# KC_BaseBoard4CompareTest-V0_2-XLR.net
KiCad netlist of a schematic drawn in Altium Designer
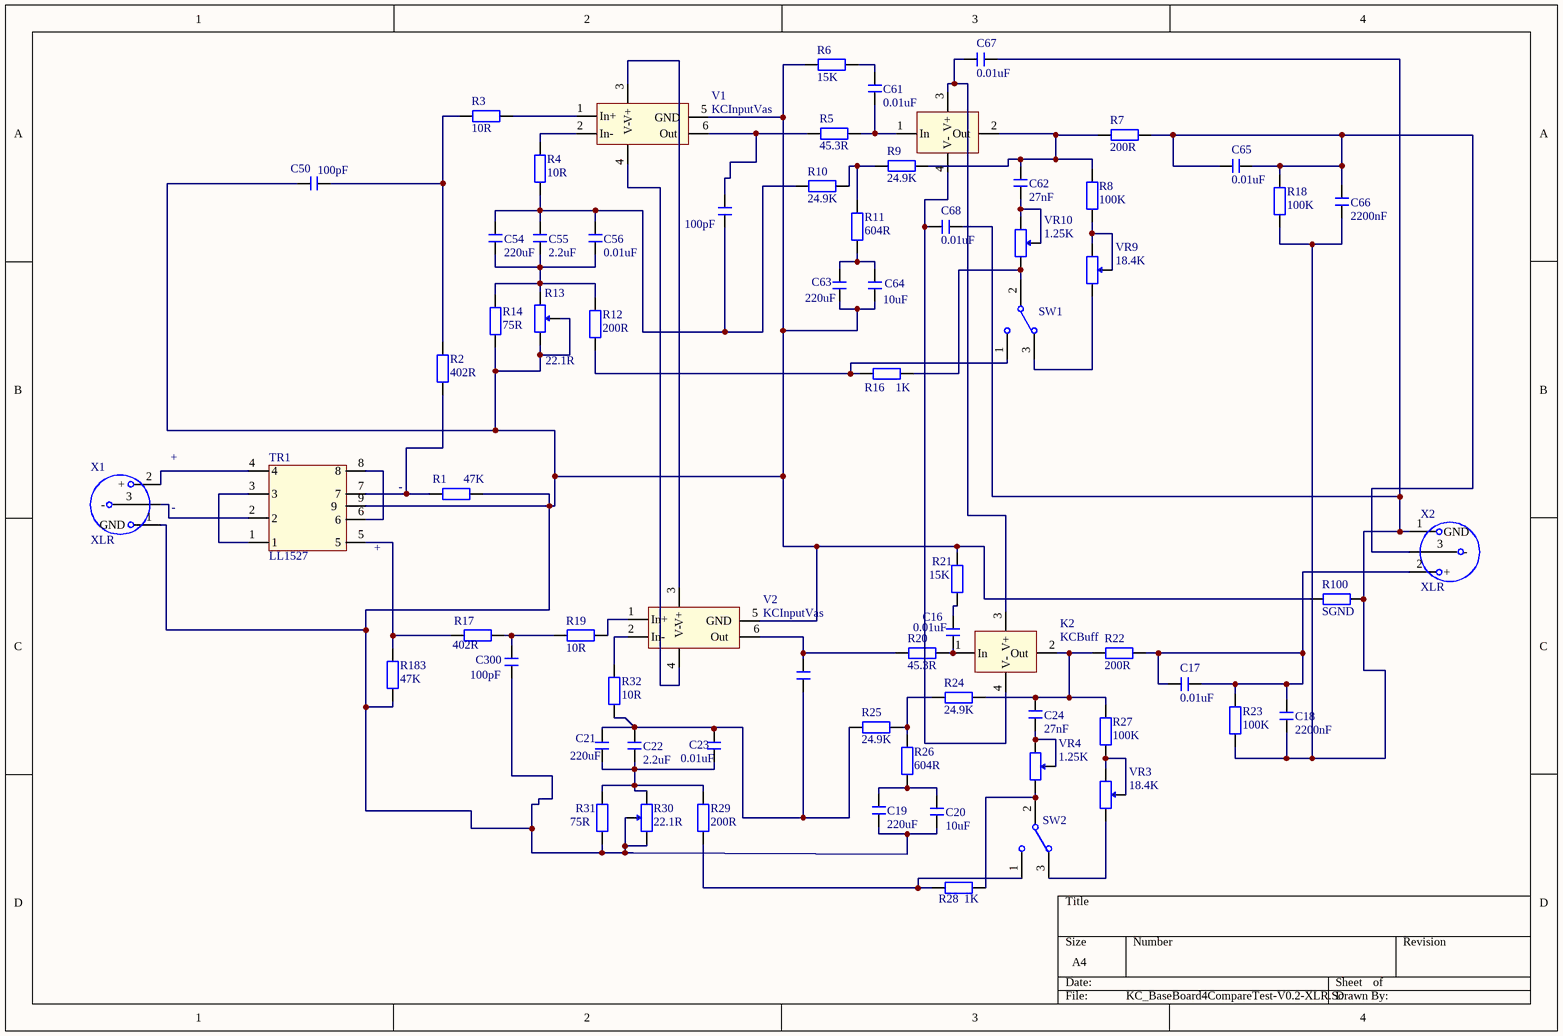
[diagram p0: KC_BaseBoard4CompareTest-V0.2-XLR.SchDoc]

(export (version "E")
  (design (tool "Eeschema 10.0.6"))
  (components
    (comp (ref "C16")
      (value "0.01uF")
      (footprint "CBB 6.3*6.3*5")
      (description "CBB电容")
      (fields (field (name "版权归属") "源创客"))
      (libsource (lib "电阻-电容-电感") (part "C-CBB"))
    )
    (comp (ref "C17")
      (value "0.01uF")
      (footprint "CBB 6.3*6.3*5")
      (description "CBB电容")
      (fields (field (name "版权归属") "源创客"))
      (libsource (lib "电阻-电容-电感") (part "C-CBB"))
    )
    (comp (ref "C18")
      (value "2200nF")
      (footprint "CBB 6.3*6.3*5")
      (description "CBB电容")
      (fields (field (name "版权归属") "源创客"))
      (libsource (lib "电阻-电容-电感") (part "C-CBB"))
    )
    (comp (ref "C19")
      (value "220uF")
      (footprint "CBB 6.3*6.3*5")
      (description "CBB电容")
      (fields (field (name "版权归属") "源创客"))
      (libsource (lib "电阻-电容-电感") (part "C-CBB"))
    )
    (comp (ref "C20")
      (value "10uF")
      (footprint "CBB 6.3*6.3*5")
      (description "CBB电容")
      (fields (field (name "版权归属") "源创客"))
      (libsource (lib "电阻-电容-电感") (part "C-CBB"))
    )
    (comp (ref "C21")
      (value "220uF")
      (footprint "CBB 6.3*6.3*5")
      (description "CBB电容")
      (fields (field (name "版权归属") "源创客"))
      (libsource (lib "电阻-电容-电感") (part "C-CBB"))
    )
    (comp (ref "C22")
      (value "2.2uF")
      (footprint "CBB 6.3*6.3*5")
      (description "CBB电容")
      (fields (field (name "版权归属") "源创客"))
      (libsource (lib "电阻-电容-电感") (part "C-CBB"))
    )
    (comp (ref "C23")
      (value "0.01uF")
      (footprint "CBB 6.3*6.3*5")
      (description "CBB电容")
      (fields (field (name "版权归属") "源创客"))
      (libsource (lib "电阻-电容-电感") (part "C-CBB"))
    )
    (comp (ref "C24")
      (value "27nF")
      (footprint "CBB 6.3*6.3*5")
      (description "CBB电容")
      (fields (field (name "版权归属") "源创客"))
      (libsource (lib "电阻-电容-电感") (part "C-CBB"))
    )
    (comp (ref "C50")
      (value "100pF")
      (footprint "CBB 6.3*6.3*5")
      (description "CBB电容")
      (fields (field (name "版权归属") "源创客"))
      (libsource (lib "电阻-电容-电感") (part "C-CBB"))
    )
    (comp (ref "C54")
      (value "220uF")
      (footprint "CBB 6.3*6.3*5")
      (description "CBB电容")
      (fields (field (name "版权归属") "源创客"))
      (libsource (lib "电阻-电容-电感") (part "C-CBB"))
    )
    (comp (ref "C55")
      (value "2.2uF")
      (footprint "CBB 6.3*6.3*5")
      (description "CBB电容")
      (fields (field (name "版权归属") "源创客"))
      (libsource (lib "电阻-电容-电感") (part "C-CBB"))
    )
    (comp (ref "C56")
      (value "0.01uF")
      (footprint "CBB 6.3*6.3*5")
      (description "CBB电容")
      (fields (field (name "版权归属") "源创客"))
      (libsource (lib "电阻-电容-电感") (part "C-CBB"))
    )
    (comp (ref "C60")
      (value "100pF")
      (footprint "CBB 6.3*6.3*5")
      (description "CBB电容")
      (fields (field (name "版权归属") "源创客"))
      (libsource (lib "电阻-电容-电感") (part "C-CBB"))
    )
    (comp (ref "C61")
      (value "0.01uF")
      (footprint "CBB 6.3*6.3*5")
      (description "CBB电容")
      (fields (field (name "版权归属") "源创客"))
      (libsource (lib "电阻-电容-电感") (part "C-CBB"))
    )
    (comp (ref "C62")
      (value "27nF")
      (footprint "CBB 6.3*6.3*5")
      (description "CBB电容")
      (fields (field (name "版权归属") "源创客"))
      (libsource (lib "电阻-电容-电感") (part "C-CBB"))
    )
    (comp (ref "C63")
      (value "220uF")
      (footprint "CBB 6.3*6.3*5")
      (description "CBB电容")
      (fields (field (name "版权归属") "源创客"))
      (libsource (lib "电阻-电容-电感") (part "C-CBB"))
    )
    (comp (ref "C64")
      (value "10uF")
      (footprint "CBB 6.3*6.3*5")
      (description "CBB电容")
      (fields (field (name "版权归属") "源创客"))
      (libsource (lib "电阻-电容-电感") (part "C-CBB"))
    )
    (comp (ref "C65")
      (value "0.01uF")
      (footprint "CBB 6.3*6.3*5")
      (description "CBB电容")
      (fields (field (name "版权归属") "源创客"))
      (libsource (lib "电阻-电容-电感") (part "C-CBB"))
    )
    (comp (ref "C66")
      (value "2200nF")
      (footprint "CBB 6.3*6.3*5")
      (description "CBB电容")
      (fields (field (name "版权归属") "源创客"))
      (libsource (lib "电阻-电容-电感") (part "C-CBB"))
    )
    (comp (ref "C67")
      (value "0.01uF")
      (footprint "CBB 6.3*6.3*5")
      (description "CBB电容")
      (fields (field (name "版权归属") "源创客"))
      (libsource (lib "电阻-电容-电感") (part "C-CBB"))
    )
    (comp (ref "C68")
      (value "0.01uF")
      (footprint "CBB 6.3*6.3*5")
      (description "CBB电容")
      (fields (field (name "版权归属") "源创客"))
      (libsource (lib "电阻-电容-电感") (part "C-CBB"))
    )
    (comp (ref "C300")
      (value "100pF")
      (footprint "CBB 6.3*6.3*5")
      (description "CBB电容")
      (fields (field (name "版权归属") "源创客"))
      (libsource (lib "电阻-电容-电感") (part "C-CBB"))
    )
    (comp (ref "C403")
      (value "100pF")
      (footprint "CBB 6.3*6.3*5")
      (description "CBB电容")
      (fields (field (name "版权归属") "源创客"))
      (libsource (lib "电阻-电容-电感") (part "C-CBB"))
    )
    (comp (ref "K1")
      (value "KCBuff")
      (footprint "KCBuff")
      (description "King Cello Buffer Stage")
      (libsource (lib "KC_amp") (part "KCBuff"))
    )
    (comp (ref "K2")
      (value "KCBuff")
      (footprint "KCBuff_M4")
      (description "King Cello Buffer Stage")
      (libsource (lib "KC_amp") (part "KCBuff"))
    )
    (comp (ref "R1")
      (value "47K")
      (footprint "RS 1/4W")
      (description "直插色环电阻")
      (fields (field (name "版权归属") "源创客"))
      (libsource (lib "电阻-电容-电感") (part "R-CRR"))
    )
    (comp (ref "R2")
      (value "402R")
      (footprint "RS 1/4W")
      (description "直插色环电阻")
      (fields (field (name "版权归属") "源创客"))
      (libsource (lib "电阻-电容-电感") (part "R-CRR"))
    )
    (comp (ref "R3")
      (value "10R")
      (footprint "RS 1/4W")
      (description "直插色环电阻")
      (fields (field (name "版权归属") "源创客"))
      (libsource (lib "电阻-电容-电感") (part "R-CRR"))
    )
    (comp (ref "R4")
      (value "10R")
      (footprint "RS 1/4W")
      (description "直插色环电阻")
      (fields (field (name "版权归属") "源创客"))
      (libsource (lib "电阻-电容-电感") (part "R-CRR"))
    )
    (comp (ref "R5")
      (value "45.3R")
      (footprint "RS 1/4W")
      (description "直插色环电阻")
      (fields (field (name "版权归属") "源创客"))
      (libsource (lib "电阻-电容-电感") (part "R-CRR"))
    )
    (comp (ref "R6")
      (value "15K")
      (footprint "RS 1/4W")
      (description "直插色环电阻")
      (fields (field (name "版权归属") "源创客"))
      (libsource (lib "电阻-电容-电感") (part "R-CRR"))
    )
    (comp (ref "R7")
      (value "200R")
      (footprint "RS 1/4W")
      (description "直插色环电阻")
      (fields (field (name "版权归属") "源创客"))
      (libsource (lib "电阻-电容-电感") (part "R-CRR"))
    )
    (comp (ref "R8")
      (value "100K")
      (footprint "RS 1/4W")
      (description "直插色环电阻")
      (fields (field (name "版权归属") "源创客"))
      (libsource (lib "电阻-电容-电感") (part "R-CRR"))
    )
    (comp (ref "R9")
      (value "24.9K")
      (footprint "RS 1/4W")
      (description "直插色环电阻")
      (fields (field (name "版权归属") "源创客"))
      (libsource (lib "电阻-电容-电感") (part "R-CRR"))
    )
    (comp (ref "R10")
      (value "24.9K")
      (footprint "RS 1/4W")
      (description "直插色环电阻")
      (fields (field (name "版权归属") "源创客"))
      (libsource (lib "电阻-电容-电感") (part "R-CRR"))
    )
    (comp (ref "R11")
      (value "604R")
      (footprint "RS 1/4W")
      (description "直插色环电阻")
      (fields (field (name "版权归属") "源创客"))
      (libsource (lib "电阻-电容-电感") (part "R-CRR"))
    )
    (comp (ref "R12")
      (value "200R")
      (footprint "RS 1/4W")
      (description "直插色环电阻")
      (fields (field (name "版权归属") "源创客"))
      (libsource (lib "电阻-电容-电感") (part "R-CRR"))
    )
    (comp (ref "R13")
      (value "22.1R")
      (footprint "RS 1/2W-VR")
      (description "直插可调电阻-顶调")
      (libsource (lib "电阻-电容-电感") (part "VR-W"))
    )
    (comp (ref "R14")
      (value "75R")
      (footprint "RS 1/4W")
      (description "直插色环电阻")
      (fields (field (name "版权归属") "源创客"))
      (libsource (lib "电阻-电容-电感") (part "R-CRR"))
    )
    (comp (ref "R16")
      (value "1K")
      (footprint "RS 1/4W")
      (description "直插色环电阻")
      (fields (field (name "版权归属") "源创客"))
      (libsource (lib "电阻-电容-电感") (part "R-CRR"))
    )
    (comp (ref "R17")
      (value "402R")
      (footprint "RS 1/4W")
      (description "直插色环电阻")
      (fields (field (name "版权归属") "源创客"))
      (libsource (lib "电阻-电容-电感") (part "R-CRR"))
    )
    (comp (ref "R18")
      (value "100K")
      (footprint "RS 1/4W")
      (description "直插色环电阻")
      (fields (field (name "版权归属") "源创客"))
      (libsource (lib "电阻-电容-电感") (part "R-CRR"))
    )
    (comp (ref "R19")
      (value "10R")
      (footprint "RS 1/4W")
      (description "直插色环电阻")
      (fields (field (name "版权归属") "源创客"))
      (libsource (lib "电阻-电容-电感") (part "R-CRR"))
    )
    (comp (ref "R20")
      (value "45.3R")
      (footprint "RS 1/4W")
      (description "直插色环电阻")
      (fields (field (name "版权归属") "源创客"))
      (libsource (lib "电阻-电容-电感") (part "R-CRR"))
    )
    (comp (ref "R21")
      (value "15K")
      (footprint "RS 1/4W")
      (description "直插色环电阻")
      (fields (field (name "版权归属") "源创客"))
      (libsource (lib "电阻-电容-电感") (part "R-CRR"))
    )
    (comp (ref "R22")
      (value "200R")
      (footprint "RS 1/4W")
      (description "直插色环电阻")
      (fields (field (name "版权归属") "源创客"))
      (libsource (lib "电阻-电容-电感") (part "R-CRR"))
    )
    (comp (ref "R23")
      (value "100K")
      (footprint "RS 1/4W")
      (description "直插色环电阻")
      (fields (field (name "版权归属") "源创客"))
      (libsource (lib "电阻-电容-电感") (part "R-CRR"))
    )
    (comp (ref "R24")
      (value "24.9K")
      (footprint "RS 1/4W")
      (description "直插色环电阻")
      (fields (field (name "版权归属") "源创客"))
      (libsource (lib "电阻-电容-电感") (part "R-CRR"))
    )
    (comp (ref "R25")
      (value "24.9K")
      (footprint "RS 1/4W")
      (description "直插色环电阻")
      (fields (field (name "版权归属") "源创客"))
      (libsource (lib "电阻-电容-电感") (part "R-CRR"))
    )
    (comp (ref "R26")
      (value "604R")
      (footprint "RS 1/4W")
      (description "直插色环电阻")
      (fields (field (name "版权归属") "源创客"))
      (libsource (lib "电阻-电容-电感") (part "R-CRR"))
    )
    (comp (ref "R27")
      (value "100K")
      (footprint "RS 1/4W")
      (description "直插色环电阻")
      (fields (field (name "版权归属") "源创客"))
      (libsource (lib "电阻-电容-电感") (part "R-CRR"))
    )
    (comp (ref "R28")
      (value "1K")
      (footprint "RS 1/4W")
      (description "直插色环电阻")
      (fields (field (name "版权归属") "源创客"))
      (libsource (lib "电阻-电容-电感") (part "R-CRR"))
    )
    (comp (ref "R29")
      (value "200R")
      (footprint "RS 1/4W")
      (description "直插色环电阻")
      (fields (field (name "版权归属") "源创客"))
      (libsource (lib "电阻-电容-电感") (part "R-CRR"))
    )
    (comp (ref "R30")
      (value "22.1R")
      (footprint "RS 1/2W-VR")
      (description "直插可调电阻-顶调")
      (libsource (lib "电阻-电容-电感") (part "VR-W"))
    )
    (comp (ref "R31")
      (value "75R")
      (footprint "RS 1/4W")
      (description "直插色环电阻")
      (fields (field (name "版权归属") "源创客"))
      (libsource (lib "电阻-电容-电感") (part "R-CRR"))
    )
    (comp (ref "R32")
      (value "10R")
      (footprint "RS 1/4W")
      (description "直插色环电阻")
      (fields (field (name "版权归属") "源创客"))
      (libsource (lib "电阻-电容-电感") (part "R-CRR"))
    )
    (comp (ref "R100")
      (value "SGND")
      (footprint "RS 1/4W")
      (description "直插色环电阻")
      (fields (field (name "版权归属") "源创客"))
      (libsource (lib "电阻-电容-电感") (part "R-CRR"))
    )
    (comp (ref "R183")
      (value "47K")
      (footprint "RS 1/4W")
      (description "直插色环电阻")
      (fields (field (name "版权归属") "源创客"))
      (libsource (lib "电阻-电容-电感") (part "R-CRR"))
    )
    (comp (ref "SW1")
      (value "SW-3P-2S")
      (footprint "SS-12D06")
      (description "3 Pin 2 Switch")
      (libsource (lib "Connectors") (part "SW-3P-2S"))
    )
    (comp (ref "SW2")
      (value "SW-3P-2S")
      (footprint "SS-12D06")
      (description "3 Pin 2 Switch")
      (libsource (lib "Connectors") (part "SW-3P-2S"))
    )
    (comp (ref "TR1")
      (value "LL1527")
      (footprint "LL1527")
      (description "Lundahl LL1527")
      (libsource (lib "KC_amp") (part "LL1527"))
    )
    (comp (ref "V1")
      (value "KCInputVas")
      (footprint "KCIn_VAS")
      (description "King Cello Input Stage and VAS")
      (libsource (lib "KC_amp") (part "KCInputVas"))
    )
    (comp (ref "V2")
      (value "KCInputVas")
      (footprint "KCIn_VAS")
      (description "King Cello Input Stage and VAS")
      (libsource (lib "KC_amp") (part "KCInputVas"))
    )
    (comp (ref "VR3")
      (value "18.4K")
      (footprint "RS 1/2W-VR")
      (description "直插可调电阻-顶调")
      (libsource (lib "电阻-电容-电感") (part "VR-W"))
    )
    (comp (ref "VR4")
      (value "1.25K")
      (footprint "RS 1/2W-VR")
      (description "直插可调电阻-顶调")
      (libsource (lib "电阻-电容-电感") (part "VR-W"))
    )
    (comp (ref "VR9")
      (value "18.4K")
      (footprint "RS 1/2W-VR")
      (description "直插可调电阻-顶调")
      (libsource (lib "电阻-电容-电感") (part "VR-W"))
    )
    (comp (ref "VR10")
      (value "1.25K")
      (footprint "RS 1/2W-VR")
      (description "直插可调电阻-顶调")
      (libsource (lib "电阻-电容-电感") (part "VR-W"))
    )
    (comp (ref "X1")
      (value "XLR")
      (footprint "XLR-Male")
      (description "3 Pin XLR")
      (libsource (lib "Connectors") (part "XLR"))
    )
    (comp (ref "X2")
      (value "XLR")
      (footprint "XLR-Male")
      (description "3 Pin XLR")
      (libsource (lib "Connectors") (part "XLR"))
    )
  )
  (nets
    (net (code "1") (name "Net-(C16-Pad2)") (class "Default")
      (node (ref "C16") (pin "2") (pinfunction "2_2") (pintype "passive"))
      (node (ref "R21") (pin "1") (pinfunction "1_1") (pintype "passive"))
    )
    (net (code "2") (name "Net-(C19-Pad1)") (class "Default")
      (node (ref "C19") (pin "1") (pinfunction "1_1") (pintype "passive"))
      (node (ref "C20") (pin "1") (pinfunction "1_1") (pintype "passive"))
      (node (ref "R26") (pin "1") (pinfunction "1_1") (pintype "passive"))
    )
    (net (code "3") (name "Net-(C21-Pad1)") (class "Default")
      (node (ref "C21") (pin "1") (pinfunction "1_1") (pintype "passive"))
      (node (ref "C22") (pin "1") (pinfunction "1_1") (pintype "passive"))
      (node (ref "C23") (pin "1") (pinfunction "1_1") (pintype "passive"))
      (node (ref "C403") (pin "1") (pinfunction "1_1") (pintype "passive"))
      (node (ref "R25") (pin "1") (pinfunction "1_1") (pintype "passive"))
      (node (ref "R32") (pin "1") (pinfunction "1_1") (pintype "passive"))
    )
    (net (code "4") (name "Net-(C21-Pad2)") (class "Default")
      (node (ref "C21") (pin "2") (pinfunction "2_2") (pintype "passive"))
      (node (ref "C22") (pin "2") (pinfunction "2_2") (pintype "passive"))
      (node (ref "C23") (pin "2") (pinfunction "2_2") (pintype "passive"))
      (node (ref "R29") (pin "2") (pinfunction "2_2") (pintype "passive"))
      (node (ref "R30") (pin "2") (pinfunction "2_2") (pintype "passive"))
      (node (ref "R31") (pin "2") (pinfunction "2_2") (pintype "passive"))
    )
    (net (code "5") (name "Net-(C24-Pad2)") (class "Default")
      (node (ref "C24") (pin "2") (pinfunction "2_2") (pintype "passive"))
      (node (ref "VR4") (pin "1") (pinfunction "1_1") (pintype "passive"))
      (node (ref "VR4") (pin "3") (pinfunction "3_3") (pintype "passive"))
    )
    (net (code "6") (name "Net-(C50-Pad2)") (class "Default")
      (node (ref "C50") (pin "2") (pinfunction "2_2") (pintype "passive"))
      (node (ref "R2") (pin "2") (pinfunction "2_2") (pintype "passive"))
      (node (ref "R3") (pin "1") (pinfunction "1_1") (pintype "passive"))
    )
    (net (code "7") (name "Net-(C54-Pad1)") (class "Default")
      (node (ref "C54") (pin "1") (pinfunction "1_1") (pintype "passive"))
      (node (ref "C55") (pin "1") (pinfunction "1_1") (pintype "passive"))
      (node (ref "C56") (pin "1") (pinfunction "1_1") (pintype "passive"))
      (node (ref "R12") (pin "1") (pinfunction "1_1") (pintype "passive"))
      (node (ref "R13") (pin "1") (pinfunction "1_1") (pintype "passive"))
      (node (ref "R14") (pin "1") (pinfunction "1_1") (pintype "passive"))
    )
    (net (code "8") (name "Net-(C54-Pad2)") (class "Default")
      (node (ref "C54") (pin "2") (pinfunction "2_2") (pintype "passive"))
      (node (ref "C55") (pin "2") (pinfunction "2_2") (pintype "passive"))
      (node (ref "C56") (pin "2") (pinfunction "2_2") (pintype "passive"))
      (node (ref "C60") (pin "1") (pinfunction "1_1") (pintype "passive"))
      (node (ref "R10") (pin "2") (pinfunction "2_2") (pintype "passive"))
      (node (ref "R4") (pin "1") (pinfunction "1_1") (pintype "passive"))
    )
    (net (code "9") (name "Net-(C61-Pad2)") (class "Default")
      (node (ref "C61") (pin "2") (pinfunction "2_2") (pintype "passive"))
      (node (ref "R6") (pin "1") (pinfunction "1_1") (pintype "passive"))
    )
    (net (code "10") (name "Net-(C62-Pad1)") (class "Default")
      (node (ref "C62") (pin "1") (pinfunction "1_1") (pintype "passive"))
      (node (ref "VR10") (pin "1") (pinfunction "1_1") (pintype "passive"))
      (node (ref "VR10") (pin "3") (pinfunction "3_3") (pintype "passive"))
    )
    (net (code "11") (name "Net-(C63-Pad2)") (class "Default")
      (node (ref "C63") (pin "2") (pinfunction "2_2") (pintype "passive"))
      (node (ref "C64") (pin "2") (pinfunction "2_2") (pintype "passive"))
      (node (ref "R11") (pin "2") (pinfunction "2_2") (pintype "passive"))
    )
    (net (code "12") (name "Net-(C300-Pad2)") (class "Default")
      (node (ref "C300") (pin "2") (pinfunction "2_2") (pintype "passive"))
      (node (ref "R17") (pin "2") (pinfunction "2_2") (pintype "passive"))
      (node (ref "R19") (pin "1") (pinfunction "1_1") (pintype "passive"))
    )
    (net (code "13") (name "Net-(K1-In)") (class "Default")
      (node (ref "C61") (pin "1") (pinfunction "1_1") (pintype "passive"))
      (node (ref "K1") (pin "1") (pinfunction "In_1") (pintype "passive"))
      (node (ref "R5") (pin "2") (pinfunction "2_2") (pintype "passive"))
    )
    (net (code "14") (name "Net-(K1-Out)") (class "Default")
      (node (ref "C62") (pin "2") (pinfunction "2_2") (pintype "passive"))
      (node (ref "K1") (pin "2") (pinfunction "Out_2") (pintype "passive"))
      (node (ref "R7") (pin "1") (pinfunction "1_1") (pintype "passive"))
      (node (ref "R8") (pin "2") (pinfunction "2_2") (pintype "passive"))
      (node (ref "R9") (pin "1") (pinfunction "1_1") (pintype "passive"))
    )
    (net (code "15") (name "Net-(K1-V+)") (class "Default")
      (node (ref "C67") (pin "1") (pinfunction "1_1") (pintype "passive"))
      (node (ref "K1") (pin "3") (pinfunction "V+_3") (pintype "passive"))
      (node (ref "K2") (pin "3") (pinfunction "V+_3") (pintype "passive"))
    )
    (net (code "16") (name "Net-(K1-V-)") (class "Default")
      (node (ref "C68") (pin "1") (pinfunction "1_1") (pintype "passive"))
      (node (ref "K1") (pin "4") (pinfunction "V-_4") (pintype "passive"))
      (node (ref "K2") (pin "4") (pinfunction "V-_4") (pintype "passive"))
    )
    (net (code "17") (name "Net-(K2-In)") (class "Default")
      (node (ref "C16") (pin "1") (pinfunction "1_1") (pintype "passive"))
      (node (ref "K2") (pin "1") (pinfunction "In_1") (pintype "passive"))
      (node (ref "R20") (pin "2") (pinfunction "2_2") (pintype "passive"))
    )
    (net (code "18") (name "Net-(K2-Out)") (class "Default")
      (node (ref "C24") (pin "1") (pinfunction "1_1") (pintype "passive"))
      (node (ref "K2") (pin "2") (pinfunction "Out_2") (pintype "passive"))
      (node (ref "R22") (pin "2") (pinfunction "2_2") (pintype "passive"))
      (node (ref "R24") (pin "2") (pinfunction "2_2") (pintype "passive"))
      (node (ref "R27") (pin "1") (pinfunction "1_1") (pintype "passive"))
    )
    (net (code "19") (name "Net-(R1-Pad1)") (class "Default")
      (node (ref "R1") (pin "1") (pinfunction "1_1") (pintype "passive"))
      (node (ref "R2") (pin "1") (pinfunction "1_1") (pintype "passive"))
      (node (ref "TR1") (pin "7") (pinfunction "7_7") (pintype "passive"))
    )
    (net (code "20") (name "Net-(R8-Pad1)") (class "Default")
      (node (ref "R8") (pin "1") (pinfunction "1_1") (pintype "passive"))
      (node (ref "VR9") (pin "1") (pinfunction "1_1") (pintype "passive"))
      (node (ref "VR9") (pin "3") (pinfunction "3_3") (pintype "passive"))
    )
    (net (code "21") (name "Net-(R10-Pad1)") (class "Default")
      (node (ref "R10") (pin "1") (pinfunction "1_1") (pintype "passive"))
      (node (ref "R11") (pin "1") (pinfunction "1_1") (pintype "passive"))
      (node (ref "R9") (pin "2") (pinfunction "2_2") (pintype "passive"))
    )
    (net (code "22") (name "Net-(R12-Pad2)") (class "Default")
      (node (ref "R12") (pin "2") (pinfunction "2_2") (pintype "passive"))
      (node (ref "R16") (pin "1") (pinfunction "1_1") (pintype "passive"))
      (node (ref "SW1") (pin "1") (pinfunction "1_1") (pintype "passive"))
    )
    (net (code "23") (name "Net-(R16-Pad2)") (class "Default")
      (node (ref "R16") (pin "2") (pinfunction "2_2") (pintype "passive"))
      (node (ref "SW1") (pin "2") (pinfunction "2_2") (pintype "passive"))
      (node (ref "VR10") (pin "2") (pinfunction "2_2") (pintype "passive"))
    )
    (net (code "24") (name "Net-(R17-Pad1)") (class "Default")
      (node (ref "R17") (pin "1") (pinfunction "1_1") (pintype "passive"))
      (node (ref "R183") (pin "2") (pinfunction "2_2") (pintype "passive"))
      (node (ref "TR1") (pin "5") (pinfunction "5_5") (pintype "passive"))
    )
    (net (code "25") (name "Net-(R24-Pad1)") (class "Default")
      (node (ref "R24") (pin "1") (pinfunction "1_1") (pintype "passive"))
      (node (ref "R25") (pin "2") (pinfunction "2_2") (pintype "passive"))
      (node (ref "R26") (pin "2") (pinfunction "2_2") (pintype "passive"))
    )
    (net (code "26") (name "Net-(R27-Pad2)") (class "Default")
      (node (ref "R27") (pin "2") (pinfunction "2_2") (pintype "passive"))
      (node (ref "VR3") (pin "1") (pinfunction "1_1") (pintype "passive"))
      (node (ref "VR3") (pin "3") (pinfunction "3_3") (pintype "passive"))
    )
    (net (code "27") (name "Net-(R28-Pad1)") (class "Default")
      (node (ref "R28") (pin "1") (pinfunction "1_1") (pintype "passive"))
      (node (ref "R29") (pin "1") (pinfunction "1_1") (pintype "passive"))
      (node (ref "SW2") (pin "1") (pinfunction "1_1") (pintype "passive"))
    )
    (net (code "28") (name "Net-(R28-Pad2)") (class "Default")
      (node (ref "R28") (pin "2") (pinfunction "2_2") (pintype "passive"))
      (node (ref "SW2") (pin "2") (pinfunction "2_2") (pintype "passive"))
      (node (ref "VR4") (pin "2") (pinfunction "2_2") (pintype "passive"))
    )
    (net (code "29") (name "Net-(SW1-Pad3)") (class "Default")
      (node (ref "SW1") (pin "3") (pinfunction "3_3") (pintype "passive"))
      (node (ref "VR9") (pin "2") (pinfunction "2_2") (pintype "passive"))
    )
    (net (code "30") (name "Net-(SW2-Pad3)") (class "Default")
      (node (ref "SW2") (pin "3") (pinfunction "3_3") (pintype "passive"))
      (node (ref "VR3") (pin "2") (pinfunction "2_2") (pintype "passive"))
    )
    (net (code "31") (name "Net-(TR1-Pad1)") (class "Default")
      (node (ref "TR1") (pin "1") (pinfunction "1_1") (pintype "passive"))
      (node (ref "TR1") (pin "3") (pinfunction "3_3") (pintype "passive"))
    )
    (net (code "32") (name "Net-(TR1-Pad6)") (class "Default")
      (node (ref "TR1") (pin "6") (pinfunction "6_6") (pintype "passive"))
      (node (ref "TR1") (pin "8") (pinfunction "8_8") (pintype "passive"))
    )
    (net (code "33") (name "Net-(V1-GND)") (class "Default")
      (node (ref "C19") (pin "2") (pinfunction "2_2") (pintype "passive"))
      (node (ref "C20") (pin "2") (pinfunction "2_2") (pintype "passive"))
      (node (ref "C300") (pin "1") (pinfunction "1_1") (pintype "passive"))
      (node (ref "C50") (pin "1") (pinfunction "1_1") (pintype "passive"))
      (node (ref "C63") (pin "1") (pinfunction "1_1") (pintype "passive"))
      (node (ref "C64") (pin "1") (pinfunction "1_1") (pintype "passive"))
      (node (ref "R1") (pin "2") (pinfunction "2_2") (pintype "passive"))
      (node (ref "R100") (pin "1") (pinfunction "1_1") (pintype "passive"))
      (node (ref "R13") (pin "2") (pinfunction "2_2") (pintype "passive"))
      (node (ref "R13") (pin "3") (pinfunction "3_3") (pintype "passive"))
      (node (ref "R14") (pin "2") (pinfunction "2_2") (pintype "passive"))
      (node (ref "R183") (pin "1") (pinfunction "1_1") (pintype "passive"))
      (node (ref "R21") (pin "2") (pinfunction "2_2") (pintype "passive"))
      (node (ref "R30") (pin "1") (pinfunction "1_1") (pintype "passive"))
      (node (ref "R30") (pin "3") (pinfunction "3_3") (pintype "passive"))
      (node (ref "R31") (pin "1") (pinfunction "1_1") (pintype "passive"))
      (node (ref "R6") (pin "2") (pinfunction "2_2") (pintype "passive"))
      (node (ref "TR1") (pin "9") (pinfunction "9_9") (pintype "passive"))
      (node (ref "V1") (pin "5") (pinfunction "GND_5") (pintype "passive"))
      (node (ref "V2") (pin "5") (pinfunction "GND_5") (pintype "passive"))
      (node (ref "X1") (pin "1") (pinfunction "GND_1") (pintype "passive"))
    )
    (net (code "34") (name "Net-(V1-In+)") (class "Default")
      (node (ref "R3") (pin "2") (pinfunction "2_2") (pintype "passive"))
      (node (ref "V1") (pin "1") (pinfunction "In+_1") (pintype "passive"))
    )
    (net (code "35") (name "Net-(V1-In-)") (class "Default")
      (node (ref "R4") (pin "2") (pinfunction "2_2") (pintype "passive"))
      (node (ref "V1") (pin "2") (pinfunction "In-_2") (pintype "passive"))
    )
    (net (code "36") (name "Net-(V1-Out)") (class "Default")
      (node (ref "C60") (pin "2") (pinfunction "2_2") (pintype "passive"))
      (node (ref "R5") (pin "1") (pinfunction "1_1") (pintype "passive"))
      (node (ref "V1") (pin "6") (pinfunction "Out_6") (pintype "passive"))
    )
    (net (code "37") (name "Net-(V1-V+)") (class "Default")
      (node (ref "V1") (pin "3") (pinfunction "V+_3") (pintype "passive"))
      (node (ref "V2") (pin "3") (pinfunction "V+_3") (pintype "passive"))
    )
    (net (code "38") (name "Net-(V1-V-)") (class "Default")
      (node (ref "V1") (pin "4") (pinfunction "V-_4") (pintype "passive"))
      (node (ref "V2") (pin "4") (pinfunction "V-_4") (pintype "passive"))
    )
    (net (code "39") (name "Net-(V2-In+)") (class "Default")
      (node (ref "R19") (pin "2") (pinfunction "2_2") (pintype "passive"))
      (node (ref "V2") (pin "1") (pinfunction "In+_1") (pintype "passive"))
    )
    (net (code "40") (name "Net-(V2-In-)") (class "Default")
      (node (ref "R32") (pin "2") (pinfunction "2_2") (pintype "passive"))
      (node (ref "V2") (pin "2") (pinfunction "In-_2") (pintype "passive"))
    )
    (net (code "41") (name "Net-(V2-Out)") (class "Default")
      (node (ref "C403") (pin "2") (pinfunction "2_2") (pintype "passive"))
      (node (ref "R20") (pin "1") (pinfunction "1_1") (pintype "passive"))
      (node (ref "V2") (pin "6") (pinfunction "Out_6") (pintype "passive"))
    )
    (net (code "42") (name "Net-(X1-+)") (class "Default")
      (node (ref "TR1") (pin "4") (pinfunction "4_4") (pintype "passive"))
      (node (ref "X1") (pin "2") (pinfunction "+_2") (pintype "passive"))
    )
    (net (code "43") (name "Net-(X1--)") (class "Default")
      (node (ref "TR1") (pin "2") (pinfunction "2_2") (pintype "passive"))
      (node (ref "X1") (pin "3") (pinfunction "-_3") (pintype "passive"))
    )
    (net (code "44") (name "Net-(X2-+)") (class "Default")
      (node (ref "C17") (pin "1") (pinfunction "1_1") (pintype "passive"))
      (node (ref "C17") (pin "2") (pinfunction "2_2") (pintype "passive"))
      (node (ref "C18") (pin "1") (pinfunction "1_1") (pintype "passive"))
      (node (ref "R22") (pin "1") (pinfunction "1_1") (pintype "passive"))
      (node (ref "R23") (pin "1") (pinfunction "1_1") (pintype "passive"))
      (node (ref "X2") (pin "2") (pinfunction "+_2") (pintype "passive"))
    )
    (net (code "45") (name "Net-(X2--)") (class "Default")
      (node (ref "C65") (pin "1") (pinfunction "1_1") (pintype "passive"))
      (node (ref "C65") (pin "2") (pinfunction "2_2") (pintype "passive"))
      (node (ref "C66") (pin "2") (pinfunction "2_2") (pintype "passive"))
      (node (ref "R18") (pin "2") (pinfunction "2_2") (pintype "passive"))
      (node (ref "R7") (pin "2") (pinfunction "2_2") (pintype "passive"))
      (node (ref "X2") (pin "3") (pinfunction "-_3") (pintype "passive"))
    )
    (net (code "46") (name "Net-(X2-GND)") (class "Default")
      (node (ref "C18") (pin "2") (pinfunction "2_2") (pintype "passive"))
      (node (ref "C66") (pin "1") (pinfunction "1_1") (pintype "passive"))
      (node (ref "C67") (pin "2") (pinfunction "2_2") (pintype "passive"))
      (node (ref "C68") (pin "2") (pinfunction "2_2") (pintype "passive"))
      (node (ref "R100") (pin "2") (pinfunction "2_2") (pintype "passive"))
      (node (ref "R18") (pin "1") (pinfunction "1_1") (pintype "passive"))
      (node (ref "R23") (pin "2") (pinfunction "2_2") (pintype "passive"))
      (node (ref "X2") (pin "1") (pinfunction "GND_1") (pintype "passive"))
    )
  )
)
